# Page04_CPU_PWR.net
KiCad netlist of a schematic drawn in Altium Designer
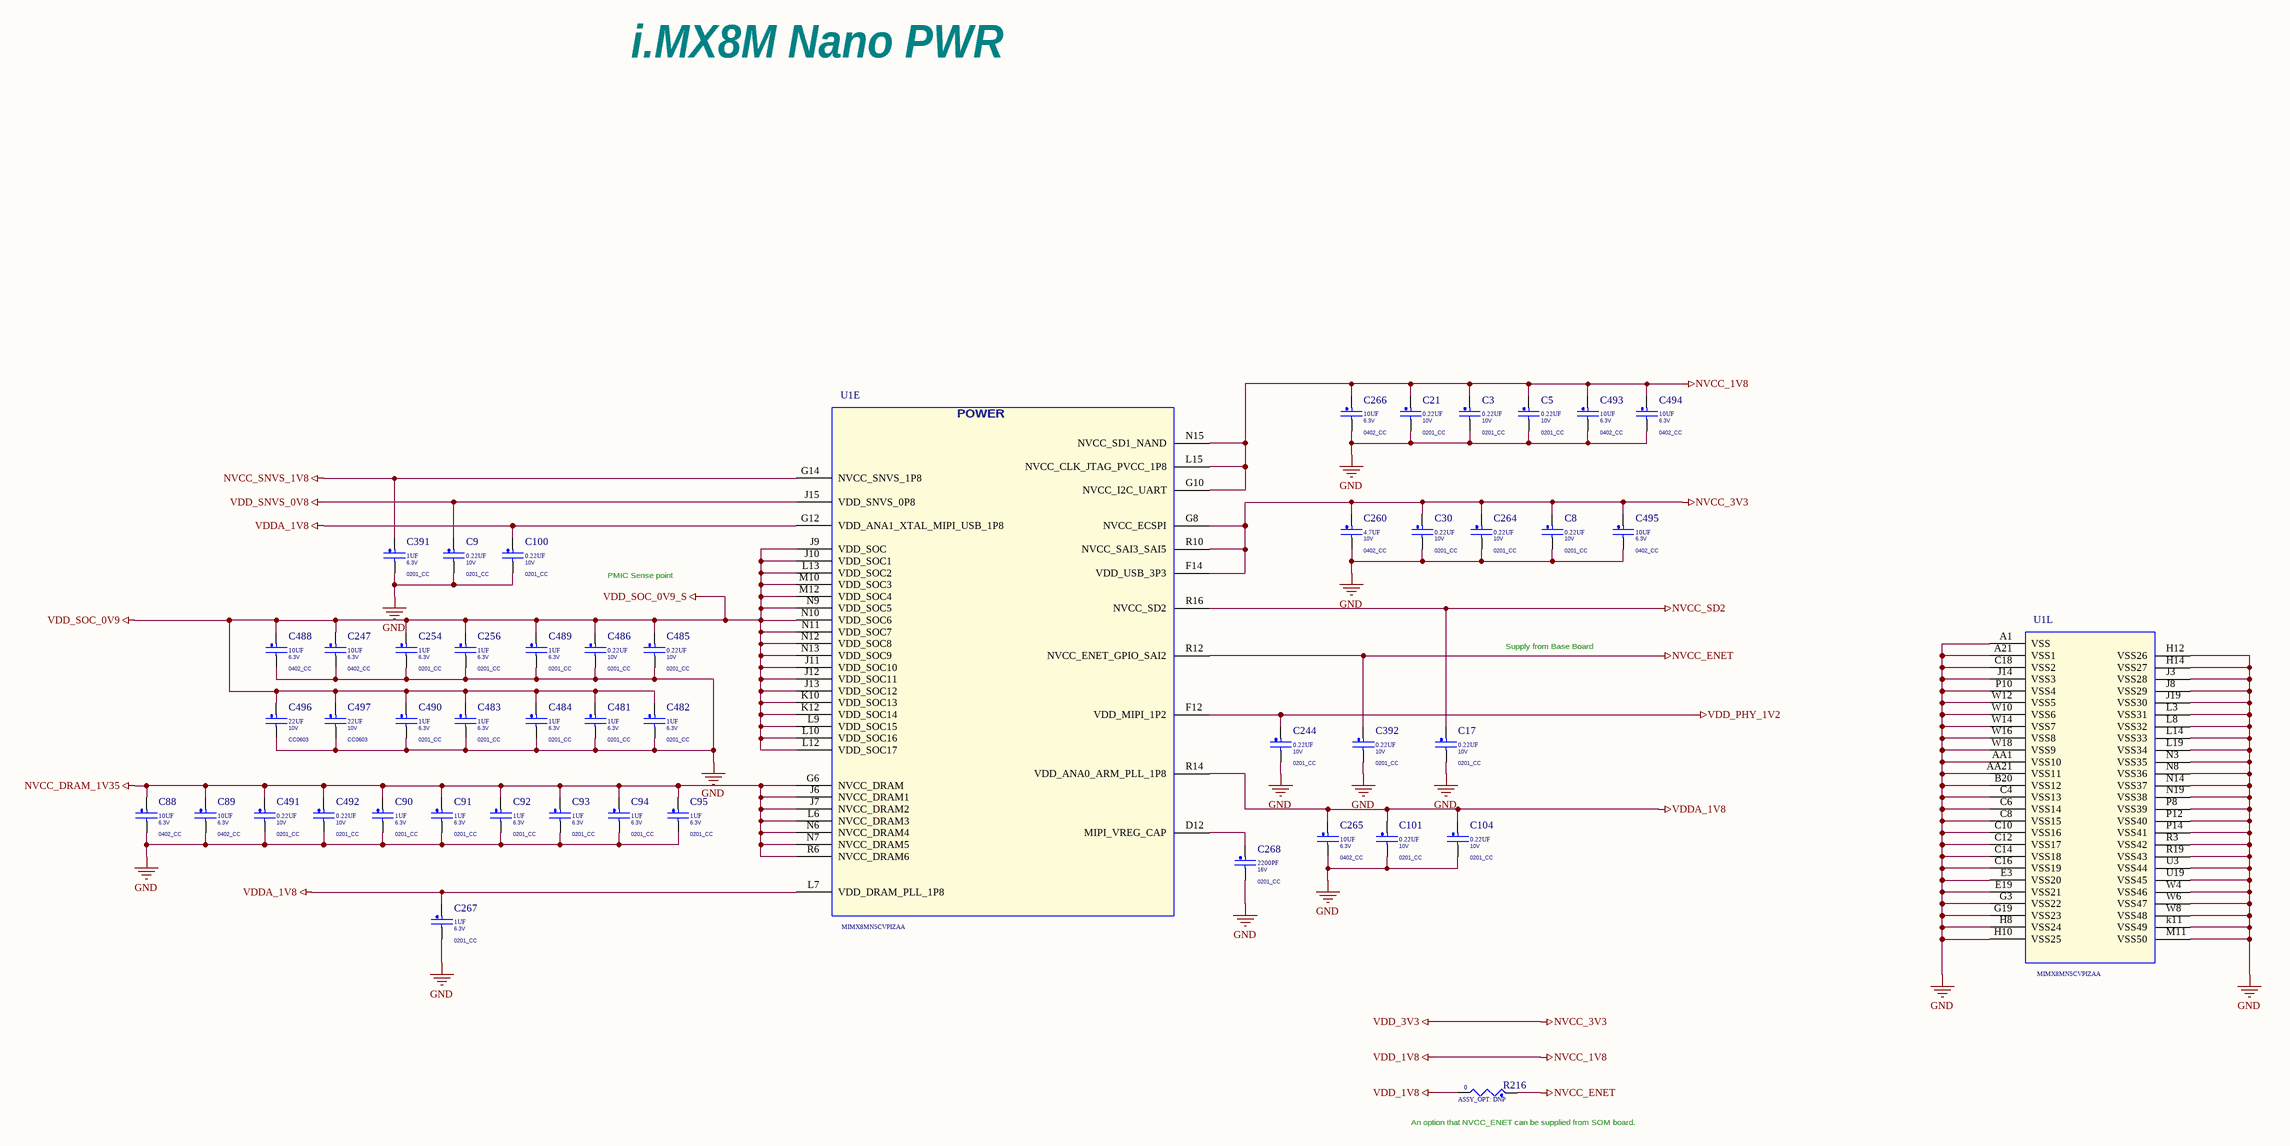
[diagram p0: Page04 CPU PWR.SchDoc]

(export (version "E")
  (design (tool "Eeschema 10.0.6"))
  (components
    (comp (ref "C3")
      (value "0.22UF")
      (footprint "0201_CC - C")
      (description "CAP CER 0.22UF 10V 20% X5R 0201")
      (fields
        (field (name "VOLTAGE") "10V")
        (field (name "TOLERANCE") "20%")
        (field (name "PCB FOOTPRINT") "0201_CC")
      )
      (libsource (lib "*") (part "CAP_NP"))
    )
    (comp (ref "C5")
      (value "0.22UF")
      (footprint "0201_CC - C")
      (description "CAP CER 0.22UF 10V 20% X5R 0201")
      (fields
        (field (name "TOLERANCE") "20%")
        (field (name "VOLTAGE") "10V")
        (field (name "PCB FOOTPRINT") "0201_CC")
      )
      (libsource (lib "*") (part "CAP_NP"))
    )
    (comp (ref "C8")
      (value "0.22UF")
      (footprint "0201_CC - C")
      (description "CAP CER 0.22UF 10V 20% X5R 0201")
      (fields
        (field (name "TOLERANCE") "20%")
        (field (name "VOLTAGE") "10V")
        (field (name "PCB FOOTPRINT") "0201_CC")
      )
      (libsource (lib "*") (part "CAP_NP"))
    )
    (comp (ref "C9")
      (value "0.22UF")
      (footprint "0201_CC - C")
      (description "CAP CER 0.22UF 10V 20% X5R 0201")
      (fields
        (field (name "VOLTAGE") "10V")
        (field (name "TOLERANCE") "20%")
        (field (name "PCB FOOTPRINT") "0201_CC")
      )
      (libsource (lib "*") (part "CAP_NP"))
    )
    (comp (ref "C17")
      (value "0.22UF")
      (footprint "0201_CC - C")
      (description "CAP CER 0.22UF 10V 20% X5R 0201")
      (fields
        (field (name "TOLERANCE") "20%")
        (field (name "VOLTAGE") "10V")
        (field (name "PCB FOOTPRINT") "0201_CC")
      )
      (libsource (lib "*") (part "CAP_NP"))
    )
    (comp (ref "C21")
      (value "0.22UF")
      (footprint "0201_CC - C")
      (description "CAP CER 0.22UF 10V 20% X5R 0201")
      (fields
        (field (name "TOLERANCE") "20%")
        (field (name "VOLTAGE") "10V")
        (field (name "PCB FOOTPRINT") "0201_CC")
      )
      (libsource (lib "*") (part "CAP_NP"))
    )
    (comp (ref "C30")
      (value "0.22UF")
      (footprint "0201_CC - C")
      (description "CAP CER 0.22UF 10V 20% X5R 0201")
      (fields
        (field (name "VOLTAGE") "10V")
        (field (name "TOLERANCE") "20%")
        (field (name "PCB FOOTPRINT") "0201_CC")
      )
      (libsource (lib "*") (part "CAP_NP"))
    )
    (comp (ref "C88")
      (value "10UF")
      (footprint "0402_CC - C")
      (description "CAP CER 10UF 6.3V 20% X5R 0402")
      (fields
        (field (name "PCB FOOTPRINT") "0402_CC")
        (field (name "TOLERANCE") "20%")
        (field (name "VOLTAGE") "6.3V")
      )
      (libsource (lib "*") (part "CAP_NP"))
    )
    (comp (ref "C89")
      (value "10UF")
      (footprint "0402_CC - C")
      (description "CAP CER 10UF 6.3V 20% X5R 0402")
      (fields
        (field (name "PCB FOOTPRINT") "0402_CC")
        (field (name "VOLTAGE") "6.3V")
        (field (name "TOLERANCE") "20%")
      )
      (libsource (lib "*") (part "CAP_NP"))
    )
    (comp (ref "C90")
      (value "1UF")
      (footprint "0201_CC - C")
      (description "CAP CER 1uF 6.3V 20% X5R 0201")
      (fields
        (field (name "PCB FOOTPRINT") "0201_CC")
        (field (name "VOLTAGE") "6.3V")
        (field (name "TOLERANCE") "20%")
      )
      (libsource (lib "*") (part "CAP_NP"))
    )
    (comp (ref "C91")
      (value "1UF")
      (footprint "0201_CC - C")
      (description "CAP CER 1uF 6.3V 20% X5R 0201")
      (fields
        (field (name "PCB FOOTPRINT") "0201_CC")
        (field (name "VOLTAGE") "6.3V")
        (field (name "TOLERANCE") "20%")
      )
      (libsource (lib "*") (part "CAP_NP"))
    )
    (comp (ref "C92")
      (value "1UF")
      (footprint "0201_CC - C")
      (description "CAP CER 1uF 6.3V 20% X5R 0201")
      (fields
        (field (name "PCB FOOTPRINT") "0201_CC")
        (field (name "VOLTAGE") "6.3V")
        (field (name "TOLERANCE") "20%")
      )
      (libsource (lib "*") (part "CAP_NP"))
    )
    (comp (ref "C93")
      (value "1UF")
      (footprint "0201_CC - C")
      (description "CAP CER 1uF 6.3V 20% X5R 0201")
      (fields
        (field (name "PCB FOOTPRINT") "0201_CC")
        (field (name "TOLERANCE") "20%")
        (field (name "VOLTAGE") "6.3V")
      )
      (libsource (lib "*") (part "CAP_NP"))
    )
    (comp (ref "C94")
      (value "1UF")
      (footprint "0201_CC - C")
      (description "CAP CER 1uF 6.3V 20% X5R 0201")
      (fields
        (field (name "PCB FOOTPRINT") "0201_CC")
        (field (name "TOLERANCE") "20%")
        (field (name "VOLTAGE") "6.3V")
      )
      (libsource (lib "*") (part "CAP_NP"))
    )
    (comp (ref "C95")
      (value "1UF")
      (footprint "0201_CC - C")
      (description "CAP CER 1uF 6.3V 20% X5R 0201")
      (fields
        (field (name "PCB FOOTPRINT") "0201_CC")
        (field (name "VOLTAGE") "6.3V")
        (field (name "TOLERANCE") "20%")
      )
      (libsource (lib "*") (part "CAP_NP"))
    )
    (comp (ref "C100")
      (value "0.22UF")
      (footprint "0201_CC - C")
      (description "CAP CER 0.22UF 10V 20% X5R 0201")
      (fields
        (field (name "TOLERANCE") "20%")
        (field (name "VOLTAGE") "10V")
        (field (name "PCB FOOTPRINT") "0201_CC")
      )
      (libsource (lib "*") (part "CAP_NP"))
    )
    (comp (ref "C101")
      (value "0.22UF")
      (footprint "0201_CC - C")
      (description "CAP CER 0.22UF 10V 20% X5R 0201")
      (fields
        (field (name "TOLERANCE") "20%")
        (field (name "VOLTAGE") "10V")
        (field (name "PCB FOOTPRINT") "0201_CC")
      )
      (libsource (lib "*") (part "CAP_NP"))
    )
    (comp (ref "C104")
      (value "0.22UF")
      (footprint "0201_CC - C")
      (description "CAP CER 0.22UF 10V 20% X5R 0201")
      (fields
        (field (name "VOLTAGE") "10V")
        (field (name "TOLERANCE") "20%")
        (field (name "PCB FOOTPRINT") "0201_CC")
      )
      (libsource (lib "*") (part "CAP_NP"))
    )
    (comp (ref "C244")
      (value "0.22UF")
      (footprint "0201_CC - C")
      (description "CAP CER 0.22UF 10V 20% X5R 0201")
      (fields
        (field (name "VOLTAGE") "10V")
        (field (name "TOLERANCE") "20%")
        (field (name "PCB FOOTPRINT") "0201_CC")
      )
      (libsource (lib "*") (part "CAP_NP"))
    )
    (comp (ref "C247")
      (value "10UF")
      (footprint "0402_CC - C")
      (description "CAP CER 10UF 6.3V 20% X5R 0402")
      (fields
        (field (name "VOLTAGE") "6.3V")
        (field (name "TOLERANCE") "20%")
        (field (name "PCB FOOTPRINT") "0402_CC")
      )
      (libsource (lib "*") (part "CAP_NP"))
    )
    (comp (ref "C254")
      (value "1UF")
      (footprint "0201_CC - C")
      (description "CAP CER 1uF 6.3V 20% X5R 0201")
      (fields
        (field (name "VOLTAGE") "6.3V")
        (field (name "TOLERANCE") "20%")
        (field (name "PCB FOOTPRINT") "0201_CC")
      )
      (libsource (lib "*") (part "CAP_NP"))
    )
    (comp (ref "C256")
      (value "1UF")
      (footprint "0201_CC - C")
      (description "CAP CER 1uF 6.3V 20% X5R 0201")
      (fields
        (field (name "TOLERANCE") "20%")
        (field (name "VOLTAGE") "6.3V")
        (field (name "PCB FOOTPRINT") "0201_CC")
      )
      (libsource (lib "*") (part "CAP_NP"))
    )
    (comp (ref "C260")
      (value "4.7UF")
      (footprint "0402_CC - C")
      (description "CAP CER 4.7uF 10V 10% X5R 0402")
      (fields
        (field (name "TOLERANCE") "10%")
        (field (name "VOLTAGE") "10V")
        (field (name "PCB FOOTPRINT") "0402_CC")
      )
      (libsource (lib "*") (part "CAP_NP"))
    )
    (comp (ref "C264")
      (value "0.22UF")
      (footprint "0201_CC - C")
      (description "CAP CER 0.22UF 10V 20% X5R 0201")
      (fields
        (field (name "TOLERANCE") "20%")
        (field (name "VOLTAGE") "10V")
        (field (name "PCB FOOTPRINT") "0201_CC")
      )
      (libsource (lib "*") (part "CAP_NP"))
    )
    (comp (ref "C265")
      (value "10UF")
      (footprint "0402_CC - C")
      (description "CAP CER 10UF 6.3V 20% X5R 0402")
      (fields
        (field (name "TOLERANCE") "20%")
        (field (name "VOLTAGE") "6.3V")
        (field (name "PCB FOOTPRINT") "0402_CC")
      )
      (libsource (lib "*") (part "CAP_NP"))
    )
    (comp (ref "C266")
      (value "10UF")
      (footprint "0402_CC - C")
      (description "CAP CER 10UF 6.3V 20% X5R 0402")
      (fields
        (field (name "TOLERANCE") "20%")
        (field (name "VOLTAGE") "6.3V")
        (field (name "PCB FOOTPRINT") "0402_CC")
      )
      (libsource (lib "*") (part "CAP_NP"))
    )
    (comp (ref "C267")
      (value "1UF")
      (footprint "0201_CC - C")
      (description "CAP CER 1uF 6.3V 20% X5R 0201")
      (fields
        (field (name "TOLERANCE") "20%")
        (field (name "VOLTAGE") "6.3V")
        (field (name "PCB FOOTPRINT") "0201_CC")
      )
      (libsource (lib "*") (part "CAP_NP"))
    )
    (comp (ref "C268")
      (value "2200PF")
      (footprint "0201_CC - C")
      (description "CAP CER 2200PF 16V 10% X7R 0201")
      (fields
        (field (name "TOLERANCE") "20%")
        (field (name "VOLTAGE") "16V")
        (field (name "PCB FOOTPRINT") "0201_CC")
      )
      (libsource (lib "*") (part "CAP_NP"))
    )
    (comp (ref "C391")
      (value "1UF")
      (footprint "0201_CC - C")
      (description "CAP CER 1uF 6.3V 20% X5R 0201")
      (fields
        (field (name "TOLERANCE") "20%")
        (field (name "VOLTAGE") "6.3V")
        (field (name "PCB FOOTPRINT") "0201_CC")
      )
      (libsource (lib "*") (part "CAP_NP"))
    )
    (comp (ref "C392")
      (value "0.22UF")
      (footprint "0201_CC - C")
      (description "CAP CER 0.22UF 10V 20% X5R 0201")
      (fields
        (field (name "VOLTAGE") "10V")
        (field (name "TOLERANCE") "20%")
        (field (name "PCB FOOTPRINT") "0201_CC")
      )
      (libsource (lib "*") (part "CAP_NP"))
    )
    (comp (ref "C481")
      (value "1UF")
      (footprint "0201_CC - C")
      (description "CAP CER 1uF 6.3V 20% X5R 0201")
      (fields
        (field (name "VOLTAGE") "6.3V")
        (field (name "TOLERANCE") "20%")
        (field (name "PCB FOOTPRINT") "0201_CC")
      )
      (libsource (lib "*") (part "CAP_NP"))
    )
    (comp (ref "C482")
      (value "1UF")
      (footprint "0201_CC - C")
      (description "CAP CER 1uF 6.3V 20% X5R 0201")
      (fields
        (field (name "VOLTAGE") "6.3V")
        (field (name "TOLERANCE") "20%")
        (field (name "PCB FOOTPRINT") "0201_CC")
      )
      (libsource (lib "*") (part "CAP_NP"))
    )
    (comp (ref "C483")
      (value "1UF")
      (footprint "0201_CC - C")
      (description "CAP CER 1uF 6.3V 20% X5R 0201")
      (fields
        (field (name "VOLTAGE") "6.3V")
        (field (name "TOLERANCE") "20%")
        (field (name "PCB FOOTPRINT") "0201_CC")
      )
      (libsource (lib "*") (part "CAP_NP"))
    )
    (comp (ref "C484")
      (value "1UF")
      (footprint "0201_CC - C")
      (description "CAP CER 1uF 6.3V 20% X5R 0201")
      (fields
        (field (name "VOLTAGE") "6.3V")
        (field (name "TOLERANCE") "20%")
        (field (name "PCB FOOTPRINT") "0201_CC")
      )
      (libsource (lib "*") (part "CAP_NP"))
    )
    (comp (ref "C485")
      (value "0.22UF")
      (footprint "0201_CC - C")
      (description "CAP CER 0.22UF 10V 20% X5R 0201")
      (fields
        (field (name "VOLTAGE") "10V")
        (field (name "TOLERANCE") "20%")
        (field (name "PCB FOOTPRINT") "0201_CC")
      )
      (libsource (lib "*") (part "CAP_NP"))
    )
    (comp (ref "C486")
      (value "0.22UF")
      (footprint "0201_CC - C")
      (description "CAP CER 0.22UF 10V 20% X5R 0201")
      (fields
        (field (name "VOLTAGE") "10V")
        (field (name "TOLERANCE") "20%")
        (field (name "PCB FOOTPRINT") "0201_CC")
      )
      (libsource (lib "*") (part "CAP_NP"))
    )
    (comp (ref "C488")
      (value "10UF")
      (footprint "0402_CC - C")
      (description "CAP CER 10UF 6.3V 20% X5R 0402")
      (fields
        (field (name "VOLTAGE") "6.3V")
        (field (name "TOLERANCE") "20%")
        (field (name "PCB FOOTPRINT") "0402_CC")
      )
      (libsource (lib "*") (part "CAP_NP"))
    )
    (comp (ref "C489")
      (value "1UF")
      (footprint "0201_CC - C")
      (description "CAP CER 1uF 6.3V 20% X5R 0201")
      (fields
        (field (name "VOLTAGE") "6.3V")
        (field (name "TOLERANCE") "20%")
        (field (name "PCB FOOTPRINT") "0201_CC")
      )
      (libsource (lib "*") (part "CAP_NP"))
    )
    (comp (ref "C490")
      (value "1UF")
      (footprint "0201_CC - C")
      (description "CAP CER 1uF 6.3V 20% X5R 0201")
      (fields
        (field (name "VOLTAGE") "6.3V")
        (field (name "TOLERANCE") "20%")
        (field (name "PCB FOOTPRINT") "0201_CC")
      )
      (libsource (lib "*") (part "CAP_NP"))
    )
    (comp (ref "C491")
      (value "0.22UF")
      (footprint "0201_CC - C")
      (description "CAP CER 0.22UF 10V 20% X5R 0201")
      (fields
        (field (name "PCB FOOTPRINT") "0201_CC")
        (field (name "TOLERANCE") "20%")
        (field (name "VOLTAGE") "10V")
      )
      (libsource (lib "*") (part "CAP_NP"))
    )
    (comp (ref "C492")
      (value "0.22UF")
      (footprint "0201_CC - C")
      (description "CAP CER 0.22UF 10V 20% X5R 0201")
      (fields
        (field (name "PCB FOOTPRINT") "0201_CC")
        (field (name "TOLERANCE") "20%")
        (field (name "VOLTAGE") "10V")
      )
      (libsource (lib "*") (part "CAP_NP"))
    )
    (comp (ref "C493")
      (value "10UF")
      (footprint "0402_CC - C")
      (description "CAP CER 10UF 6.3V 20% X5R 0402")
      (fields
        (field (name "TOLERANCE") "20%")
        (field (name "VOLTAGE") "6.3V")
        (field (name "PCB FOOTPRINT") "0402_CC")
      )
      (libsource (lib "*") (part "CAP_NP"))
    )
    (comp (ref "C494")
      (value "10UF")
      (footprint "0402_CC - C")
      (description "CAP CER 10UF 6.3V 20% X5R 0402")
      (fields
        (field (name "TOLERANCE") "20%")
        (field (name "VOLTAGE") "6.3V")
        (field (name "PCB FOOTPRINT") "0402_CC")
      )
      (libsource (lib "*") (part "CAP_NP"))
    )
    (comp (ref "C495")
      (value "10UF")
      (footprint "0402_CC - C")
      (description "CAP CER 10UF 6.3V 20% X5R 0402")
      (fields
        (field (name "VOLTAGE") "6.3V")
        (field (name "TOLERANCE") "20%")
        (field (name "PCB FOOTPRINT") "0402_CC")
      )
      (libsource (lib "*") (part "CAP_NP"))
    )
    (comp (ref "C496")
      (value "22UF")
      (footprint "0603_CC")
      (description "CAP CER 22uF 10V 20% X5R 0603")
      (fields
        (field (name "VOLTAGE") "10V")
        (field (name "TOLERANCE") "20%")
        (field (name "PCB FOOTPRINT") "CC0603")
      )
      (libsource (lib "*") (part "CAP_NP"))
    )
    (comp (ref "C497")
      (value "22UF")
      (footprint "0603_CC")
      (description "CAP CER 22uF 10V 20% X5R 0603")
      (fields
        (field (name "VOLTAGE") "10V")
        (field (name "TOLERANCE") "20%")
        (field (name "PCB FOOTPRINT") "CC0603")
      )
      (libsource (lib "*") (part "CAP_NP"))
    )
    (comp (ref "R216")
      (value "0")
      (footprint "0402_CC_RES")
      (description "RES MF ZERO OHM 1/16W 5% 0402")
      (fields
        (field (name "ASSY_OPT") "DNP")
        (field (name "TOLERANCE") "5%")
        (field (name "VOLTAGE") "1/16W")
      )
      (libsource (lib "*") (part "RES"))
    )
    (comp (ref "U1")
      (value "MIMX8MN5CVPIZAA")
      (footprint "BGA306C50P21X21_1100X1100X101")
      (description "IC CPU QUAD CORTEX A53+M7 1.4GHZ -- BGA306")
      (libsource (lib "*") (part "MIMX8MN"))
    )
  )
  (nets
    (net (code "1") (name "GND") (class "Default")
      (node (ref "C100") (pin "2") (pinfunction "2_2") (pintype "passive"))
      (node (ref "C101") (pin "2") (pinfunction "2_2") (pintype "passive"))
      (node (ref "C104") (pin "2") (pinfunction "2_2") (pintype "passive"))
      (node (ref "C17") (pin "2") (pinfunction "2_2") (pintype "passive"))
      (node (ref "C21") (pin "2") (pinfunction "2_2") (pintype "passive"))
      (node (ref "C244") (pin "2") (pinfunction "2_2") (pintype "passive"))
      (node (ref "C247") (pin "2") (pinfunction "2_2") (pintype "passive"))
      (node (ref "C254") (pin "2") (pinfunction "2_2") (pintype "passive"))
      (node (ref "C256") (pin "2") (pinfunction "2_2") (pintype "passive"))
      (node (ref "C260") (pin "2") (pinfunction "2_2") (pintype "passive"))
      (node (ref "C264") (pin "2") (pinfunction "2_2") (pintype "passive"))
      (node (ref "C265") (pin "2") (pinfunction "2_2") (pintype "passive"))
      (node (ref "C266") (pin "2") (pinfunction "2_2") (pintype "passive"))
      (node (ref "C267") (pin "2") (pinfunction "2_2") (pintype "passive"))
      (node (ref "C268") (pin "2") (pinfunction "2_2") (pintype "passive"))
      (node (ref "C3") (pin "2") (pinfunction "2_2") (pintype "passive"))
      (node (ref "C30") (pin "2") (pinfunction "2_2") (pintype "passive"))
      (node (ref "C391") (pin "2") (pinfunction "2_2") (pintype "passive"))
      (node (ref "C392") (pin "2") (pinfunction "2_2") (pintype "passive"))
      (node (ref "C481") (pin "2") (pinfunction "2_2") (pintype "passive"))
      (node (ref "C482") (pin "2") (pinfunction "2_2") (pintype "passive"))
      (node (ref "C483") (pin "2") (pinfunction "2_2") (pintype "passive"))
      (node (ref "C484") (pin "2") (pinfunction "2_2") (pintype "passive"))
      (node (ref "C485") (pin "2") (pinfunction "2_2") (pintype "passive"))
      (node (ref "C486") (pin "2") (pinfunction "2_2") (pintype "passive"))
      (node (ref "C488") (pin "2") (pinfunction "2_2") (pintype "passive"))
      (node (ref "C489") (pin "2") (pinfunction "2_2") (pintype "passive"))
      (node (ref "C490") (pin "2") (pinfunction "2_2") (pintype "passive"))
      (node (ref "C491") (pin "2") (pinfunction "2_2") (pintype "passive"))
      (node (ref "C492") (pin "2") (pinfunction "2_2") (pintype "passive"))
      (node (ref "C493") (pin "2") (pinfunction "2_2") (pintype "passive"))
      (node (ref "C494") (pin "2") (pinfunction "2_2") (pintype "passive"))
      (node (ref "C495") (pin "2") (pinfunction "2_2") (pintype "passive"))
      (node (ref "C496") (pin "2") (pinfunction "2_2") (pintype "passive"))
      (node (ref "C497") (pin "2") (pinfunction "2_2") (pintype "passive"))
      (node (ref "C5") (pin "2") (pinfunction "2_2") (pintype "passive"))
      (node (ref "C8") (pin "2") (pinfunction "2_2") (pintype "passive"))
      (node (ref "C88") (pin "2") (pinfunction "2_2") (pintype "passive"))
      (node (ref "C89") (pin "2") (pinfunction "2_2") (pintype "passive"))
      (node (ref "C9") (pin "2") (pinfunction "2_2") (pintype "passive"))
      (node (ref "C90") (pin "2") (pinfunction "2_2") (pintype "passive"))
      (node (ref "C91") (pin "2") (pinfunction "2_2") (pintype "passive"))
      (node (ref "C92") (pin "2") (pinfunction "2_2") (pintype "passive"))
      (node (ref "C93") (pin "2") (pinfunction "2_2") (pintype "passive"))
      (node (ref "C94") (pin "2") (pinfunction "2_2") (pintype "passive"))
      (node (ref "C95") (pin "2") (pinfunction "2_2") (pintype "passive"))
      (node (ref "U1") (pin "A1") (pinfunction "VSS_A1") (pintype "passive"))
      (node (ref "U1") (pin "A21") (pinfunction "VSS1_A21") (pintype "passive"))
      (node (ref "U1") (pin "AA1") (pinfunction "VSS10_AA1") (pintype "passive"))
      (node (ref "U1") (pin "AA21") (pinfunction "VSS11_AA21") (pintype "passive"))
      (node (ref "U1") (pin "B20") (pinfunction "VSS12_B20") (pintype "passive"))
      (node (ref "U1") (pin "C10") (pinfunction "VSS16_C10") (pintype "passive"))
      (node (ref "U1") (pin "C12") (pinfunction "VSS17_C12") (pintype "passive"))
      (node (ref "U1") (pin "C14") (pinfunction "VSS18_C14") (pintype "passive"))
      (node (ref "U1") (pin "C16") (pinfunction "VSS19_C16") (pintype "passive"))
      (node (ref "U1") (pin "C18") (pinfunction "VSS2_C18") (pintype "passive"))
      (node (ref "U1") (pin "C4") (pinfunction "VSS13_C4") (pintype "passive"))
      (node (ref "U1") (pin "C6") (pinfunction "VSS14_C6") (pintype "passive"))
      (node (ref "U1") (pin "C8") (pinfunction "VSS15_C8") (pintype "passive"))
      (node (ref "U1") (pin "E19") (pinfunction "VSS21_E19") (pintype "passive"))
      (node (ref "U1") (pin "E3") (pinfunction "VSS20_E3") (pintype "passive"))
      (node (ref "U1") (pin "G19") (pinfunction "VSS23_G19") (pintype "passive"))
      (node (ref "U1") (pin "G3") (pinfunction "VSS22_G3") (pintype "passive"))
      (node (ref "U1") (pin "H10") (pinfunction "VSS25_H10") (pintype "passive"))
      (node (ref "U1") (pin "H12") (pinfunction "VSS26_H12") (pintype "passive"))
      (node (ref "U1") (pin "H14") (pinfunction "VSS27_H14") (pintype "passive"))
      (node (ref "U1") (pin "H8") (pinfunction "VSS24_H8") (pintype "passive"))
      (node (ref "U1") (pin "J14") (pinfunction "VSS3_J14") (pintype "passive"))
      (node (ref "U1") (pin "J19") (pinfunction "VSS30_J19") (pintype "passive"))
      (node (ref "U1") (pin "J3") (pinfunction "VSS28_J3") (pintype "passive"))
      (node (ref "U1") (pin "J8") (pinfunction "VSS29_J8") (pintype "passive"))
      (node (ref "U1") (pin "L14") (pinfunction "VSS33_L14") (pintype "passive"))
      (node (ref "U1") (pin "L19") (pinfunction "VSS34_L19") (pintype "passive"))
      (node (ref "U1") (pin "L3") (pinfunction "VSS31_L3") (pintype "passive"))
      (node (ref "U1") (pin "L8") (pinfunction "VSS32_L8") (pintype "passive"))
      (node (ref "U1") (pin "M11") (pinfunction "VSS50_M11") (pintype "passive"))
      (node (ref "U1") (pin "N14") (pinfunction "VSS37_N14") (pintype "passive"))
      (node (ref "U1") (pin "N19") (pinfunction "VSS38_N19") (pintype "passive"))
      (node (ref "U1") (pin "N3") (pinfunction "VSS35_N3") (pintype "passive"))
      (node (ref "U1") (pin "N8") (pinfunction "VSS36_N8") (pintype "passive"))
      (node (ref "U1") (pin "P10") (pinfunction "VSS4_P10") (pintype "passive"))
      (node (ref "U1") (pin "P12") (pinfunction "VSS40_P12") (pintype "passive"))
      (node (ref "U1") (pin "P14") (pinfunction "VSS41_P14") (pintype "passive"))
      (node (ref "U1") (pin "P8") (pinfunction "VSS39_P8") (pintype "passive"))
      (node (ref "U1") (pin "R19") (pinfunction "VSS43_R19") (pintype "passive"))
      (node (ref "U1") (pin "R3") (pinfunction "VSS42_R3") (pintype "passive"))
      (node (ref "U1") (pin "U19") (pinfunction "VSS45_U19") (pintype "passive"))
      (node (ref "U1") (pin "U3") (pinfunction "VSS44_U3") (pintype "passive"))
      (node (ref "U1") (pin "W10") (pinfunction "VSS6_W10") (pintype "passive"))
      (node (ref "U1") (pin "W12") (pinfunction "VSS5_W12") (pintype "passive"))
      (node (ref "U1") (pin "W14") (pinfunction "VSS7_W14") (pintype "passive"))
      (node (ref "U1") (pin "W16") (pinfunction "VSS8_W16") (pintype "passive"))
      (node (ref "U1") (pin "W18") (pinfunction "VSS9_W18") (pintype "passive"))
      (node (ref "U1") (pin "W4") (pinfunction "VSS46_W4") (pintype "passive"))
      (node (ref "U1") (pin "W6") (pinfunction "VSS47_W6") (pintype "passive"))
      (node (ref "U1") (pin "W8") (pinfunction "VSS48_W8") (pintype "passive"))
      (node (ref "U1") (pin "k11") (pinfunction "VSS49_k11") (pintype "passive"))
    )
    (net (code "2") (name "NVCC_1V8") (class "Default")
      (node (ref "C21") (pin "1") (pinfunction "1_1") (pintype "passive"))
      (node (ref "C266") (pin "1") (pinfunction "1_1") (pintype "passive"))
      (node (ref "C3") (pin "1") (pinfunction "1_1") (pintype "passive"))
      (node (ref "C493") (pin "1") (pinfunction "1_1") (pintype "passive"))
      (node (ref "C494") (pin "1") (pinfunction "1_1") (pintype "passive"))
      (node (ref "C5") (pin "1") (pinfunction "1_1") (pintype "passive"))
      (node (ref "R216") (pin "2") (pinfunction "2_2") (pintype "passive"))
      (node (ref "U1") (pin "G10") (pinfunction "NVCC_I2C_UART_G10") (pintype "passive"))
      (node (ref "U1") (pin "L15") (pinfunction "NVCC_CLK_JTAG_PVCC_1P8_L15") (pintype "passive"))
      (node (ref "U1") (pin "N15") (pinfunction "NVCC_SD1_NAND_N15") (pintype "passive"))
    )
    (net (code "3") (name "NVCC_3V3") (class "Default")
      (node (ref "C260") (pin "1") (pinfunction "1_1") (pintype "passive"))
      (node (ref "C264") (pin "1") (pinfunction "1_1") (pintype "passive"))
      (node (ref "C30") (pin "1") (pinfunction "1_1") (pintype "passive"))
      (node (ref "C495") (pin "1") (pinfunction "1_1") (pintype "passive"))
      (node (ref "C8") (pin "1") (pinfunction "1_1") (pintype "passive"))
      (node (ref "U1") (pin "F14") (pinfunction "VDD_USB_3P3_F14") (pintype "passive"))
      (node (ref "U1") (pin "G8") (pinfunction "NVCC_ECSPI_G8") (pintype "passive"))
      (node (ref "U1") (pin "R10") (pinfunction "NVCC_SAI3_SAI5_R10") (pintype "passive"))
    )
    (net (code "4") (name "NVCC_DRAM_1V35") (class "Default")
      (node (ref "C491") (pin "1") (pinfunction "1_1") (pintype "passive"))
      (node (ref "C492") (pin "1") (pinfunction "1_1") (pintype "passive"))
      (node (ref "C88") (pin "1") (pinfunction "1_1") (pintype "passive"))
      (node (ref "C89") (pin "1") (pinfunction "1_1") (pintype "passive"))
      (node (ref "C90") (pin "1") (pinfunction "1_1") (pintype "passive"))
      (node (ref "C91") (pin "1") (pinfunction "1_1") (pintype "passive"))
      (node (ref "C92") (pin "1") (pinfunction "1_1") (pintype "passive"))
      (node (ref "C93") (pin "1") (pinfunction "1_1") (pintype "passive"))
      (node (ref "C94") (pin "1") (pinfunction "1_1") (pintype "passive"))
      (node (ref "C95") (pin "1") (pinfunction "1_1") (pintype "passive"))
      (node (ref "U1") (pin "G6") (pinfunction "NVCC_DRAM_G6") (pintype "passive"))
      (node (ref "U1") (pin "J6") (pinfunction "NVCC_DRAM1_J6") (pintype "passive"))
      (node (ref "U1") (pin "J7") (pinfunction "NVCC_DRAM2_J7") (pintype "passive"))
      (node (ref "U1") (pin "L6") (pinfunction "NVCC_DRAM3_L6") (pintype "passive"))
      (node (ref "U1") (pin "N6") (pinfunction "NVCC_DRAM4_N6") (pintype "passive"))
      (node (ref "U1") (pin "N7") (pinfunction "NVCC_DRAM5_N7") (pintype "passive"))
      (node (ref "U1") (pin "R6") (pinfunction "NVCC_DRAM6_R6") (pintype "passive"))
    )
    (net (code "5") (name "NVCC_ENET") (class "Default")
      (node (ref "C392") (pin "1") (pinfunction "1_1") (pintype "passive"))
      (node (ref "R216") (pin "1") (pinfunction "1_1") (pintype "passive"))
      (node (ref "U1") (pin "R12") (pinfunction "NVCC_ENET_GPIO_SAI2_R12") (pintype "passive"))
    )
    (net (code "6") (name "NVCC_SD2") (class "Default")
      (node (ref "C17") (pin "1") (pinfunction "1_1") (pintype "passive"))
      (node (ref "U1") (pin "R16") (pinfunction "NVCC_SD2_R16") (pintype "passive"))
    )
    (net (code "7") (name "NVCC_SNVS_1V8") (class "Default")
      (node (ref "C391") (pin "1") (pinfunction "1_1") (pintype "passive"))
      (node (ref "U1") (pin "G14") (pinfunction "NVCC_SNVS_1P8_G14") (pintype "passive"))
    )
    (net (code "8") (name "Net-(U1E-MIPI_VREG_CAP)") (class "Default")
      (node (ref "C268") (pin "1") (pinfunction "1_1") (pintype "passive"))
      (node (ref "U1") (pin "D12") (pinfunction "MIPI_VREG_CAP_D12") (pintype "passive"))
    )
    (net (code "9") (name "VDDA_1V8") (class "Default")
      (node (ref "C100") (pin "1") (pinfunction "1_1") (pintype "passive"))
      (node (ref "C101") (pin "1") (pinfunction "1_1") (pintype "passive"))
      (node (ref "C104") (pin "1") (pinfunction "1_1") (pintype "passive"))
      (node (ref "C265") (pin "1") (pinfunction "1_1") (pintype "passive"))
      (node (ref "C267") (pin "1") (pinfunction "1_1") (pintype "passive"))
      (node (ref "U1") (pin "G12") (pinfunction "VDD_ANA1_XTAL_MIPI_USB_1P8_G12") (pintype "passive"))
      (node (ref "U1") (pin "L7") (pinfunction "VDD_DRAM_PLL_1P8_L7") (pintype "passive"))
      (node (ref "U1") (pin "R14") (pinfunction "VDD_ANA0_ARM_PLL_1P8_R14") (pintype "passive"))
    )
    (net (code "10") (name "VDD_PHY_1V2") (class "Default")
      (node (ref "C244") (pin "1") (pinfunction "1_1") (pintype "passive"))
      (node (ref "U1") (pin "F12") (pinfunction "VDD_MIPI_1P2_F12") (pintype "passive"))
    )
    (net (code "11") (name "VDD_SNVS_0V8") (class "Default")
      (node (ref "C9") (pin "1") (pinfunction "1_1") (pintype "passive"))
      (node (ref "U1") (pin "J15") (pinfunction "VDD_SNVS_0P8_J15") (pintype "passive"))
    )
    (net (code "12") (name "VDD_SOC_0V9") (class "Default")
      (node (ref "C247") (pin "1") (pinfunction "1_1") (pintype "passive"))
      (node (ref "C254") (pin "1") (pinfunction "1_1") (pintype "passive"))
      (node (ref "C256") (pin "1") (pinfunction "1_1") (pintype "passive"))
      (node (ref "C481") (pin "1") (pinfunction "1_1") (pintype "passive"))
      (node (ref "C482") (pin "1") (pinfunction "1_1") (pintype "passive"))
      (node (ref "C483") (pin "1") (pinfunction "1_1") (pintype "passive"))
      (node (ref "C484") (pin "1") (pinfunction "1_1") (pintype "passive"))
      (node (ref "C485") (pin "1") (pinfunction "1_1") (pintype "passive"))
      (node (ref "C486") (pin "1") (pinfunction "1_1") (pintype "passive"))
      (node (ref "C488") (pin "1") (pinfunction "1_1") (pintype "passive"))
      (node (ref "C489") (pin "1") (pinfunction "1_1") (pintype "passive"))
      (node (ref "C490") (pin "1") (pinfunction "1_1") (pintype "passive"))
      (node (ref "C496") (pin "1") (pinfunction "1_1") (pintype "passive"))
      (node (ref "C497") (pin "1") (pinfunction "1_1") (pintype "passive"))
      (node (ref "U1") (pin "J10") (pinfunction "VDD_SOC1_J10") (pintype "passive"))
      (node (ref "U1") (pin "J11") (pinfunction "VDD_SOC10_J11") (pintype "passive"))
      (node (ref "U1") (pin "J12") (pinfunction "VDD_SOC11_J12") (pintype "passive"))
      (node (ref "U1") (pin "J13") (pinfunction "VDD_SOC12_J13") (pintype "passive"))
      (node (ref "U1") (pin "J9") (pinfunction "VDD_SOC_J9") (pintype "passive"))
      (node (ref "U1") (pin "K10") (pinfunction "VDD_SOC13_K10") (pintype "passive"))
      (node (ref "U1") (pin "K12") (pinfunction "VDD_SOC14_K12") (pintype "passive"))
      (node (ref "U1") (pin "L10") (pinfunction "VDD_SOC16_L10") (pintype "passive"))
      (node (ref "U1") (pin "L12") (pinfunction "VDD_SOC17_L12") (pintype "passive"))
      (node (ref "U1") (pin "L13") (pinfunction "VDD_SOC2_L13") (pintype "passive"))
      (node (ref "U1") (pin "L9") (pinfunction "VDD_SOC15_L9") (pintype "passive"))
      (node (ref "U1") (pin "M10") (pinfunction "VDD_SOC3_M10") (pintype "passive"))
      (node (ref "U1") (pin "M12") (pinfunction "VDD_SOC4_M12") (pintype "passive"))
      (node (ref "U1") (pin "N10") (pinfunction "VDD_SOC6_N10") (pintype "passive"))
      (node (ref "U1") (pin "N11") (pinfunction "VDD_SOC7_N11") (pintype "passive"))
      (node (ref "U1") (pin "N12") (pinfunction "VDD_SOC8_N12") (pintype "passive"))
      (node (ref "U1") (pin "N13") (pinfunction "VDD_SOC9_N13") (pintype "passive"))
      (node (ref "U1") (pin "N9") (pinfunction "VDD_SOC5_N9") (pintype "passive"))
    )
  )
)
